# SerialController.net
KiCad netlist of a schematic drawn in EAGLE
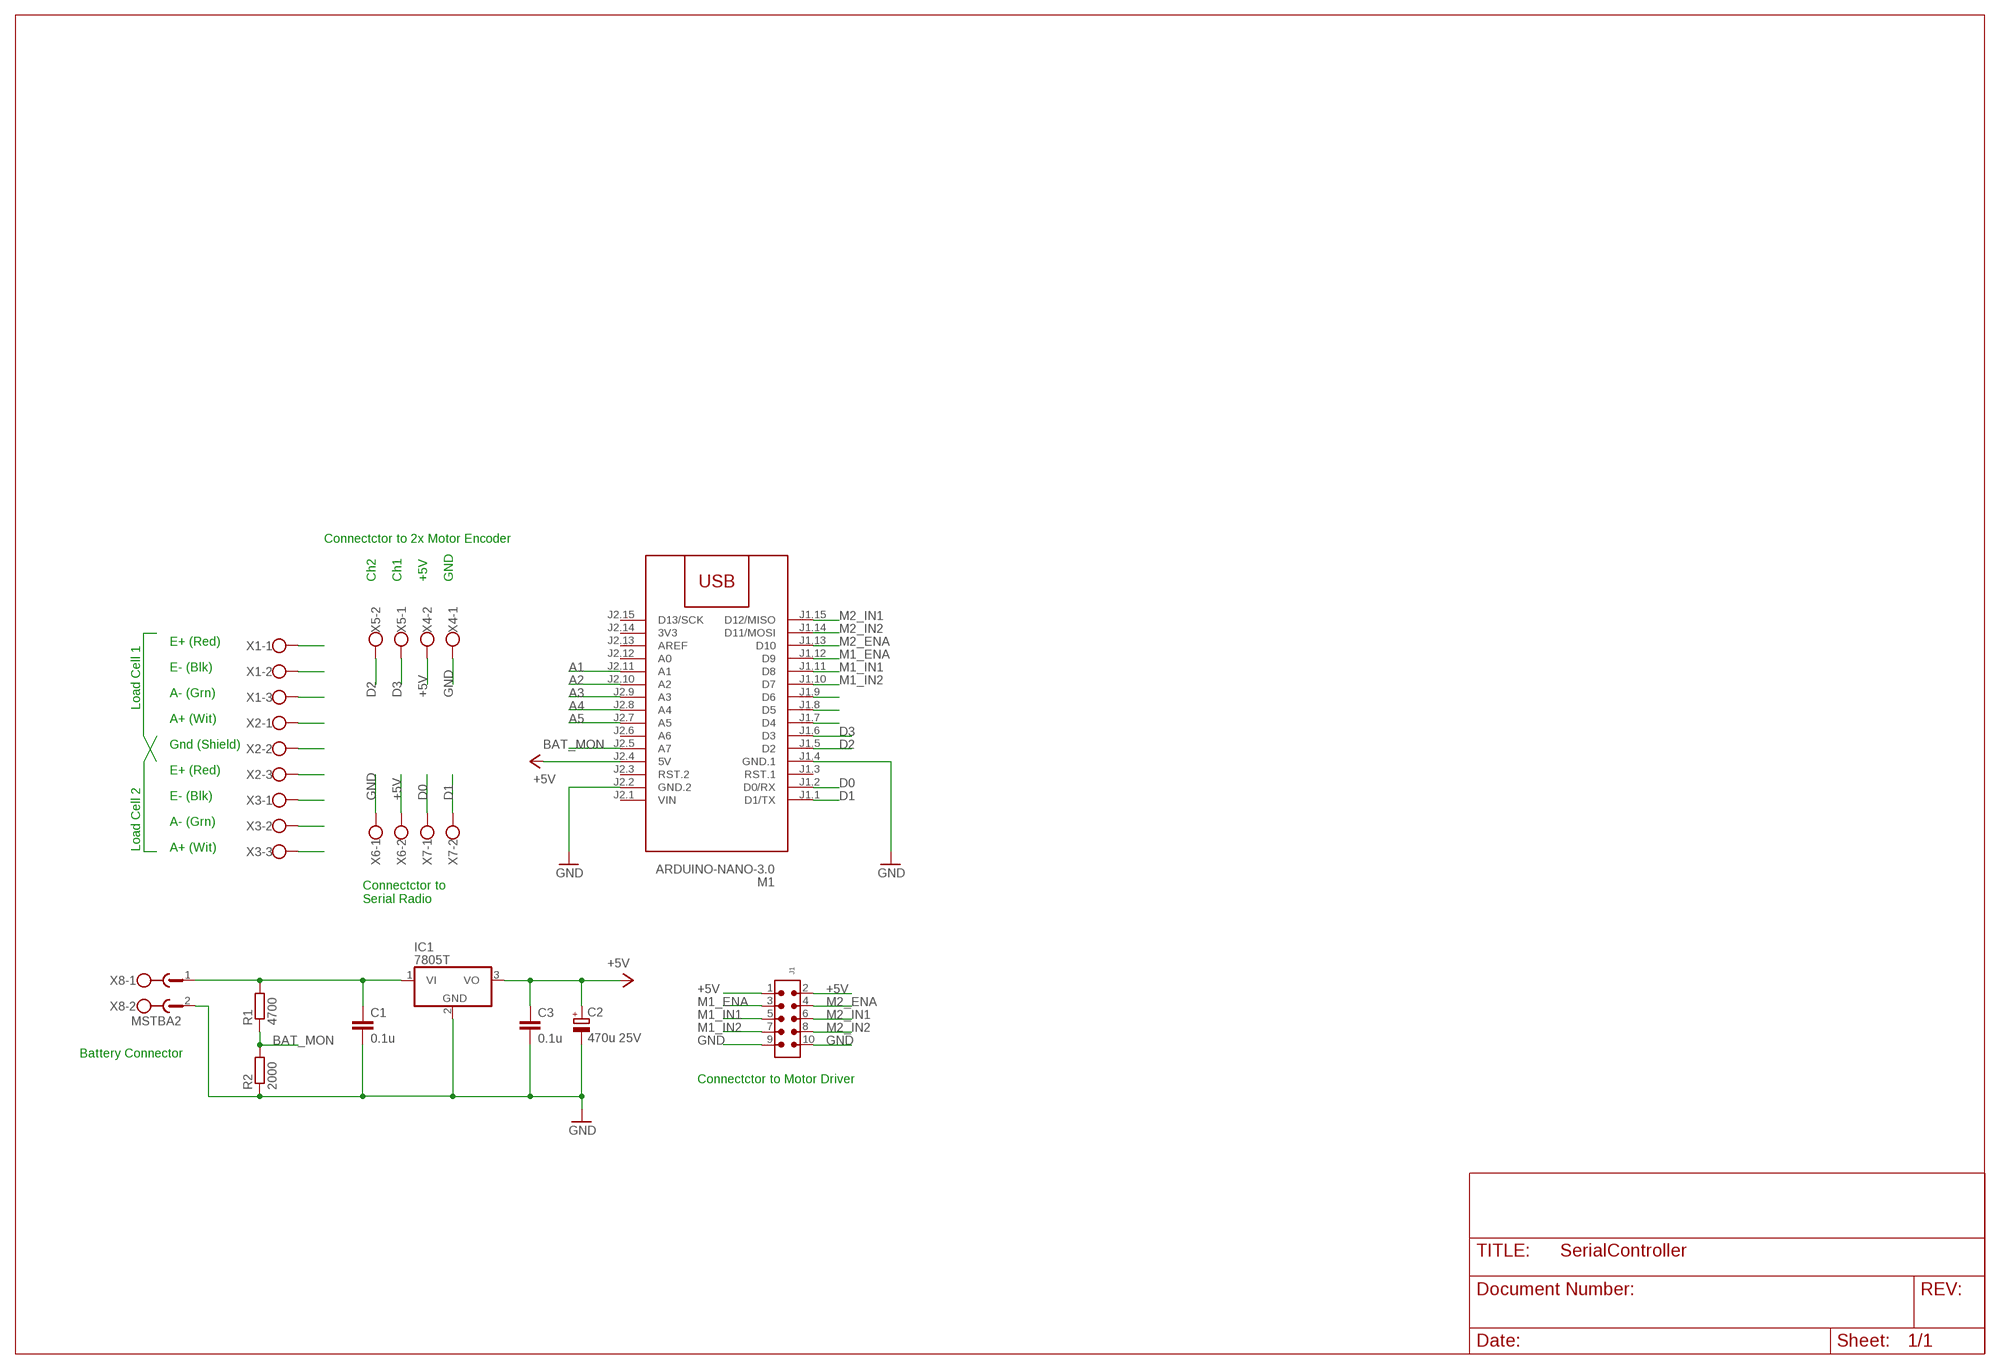
[diagram p0: schematic, sheet 1]

(export (version "E")
  (design (tool "Eeschema 10.0.6"))
  (components
    (comp (ref "C1")
      (value "0.1u")
      (footprint "eagle-import:C050-030X075")
      (libsource (lib "eagle-import") (part "C-EU050-030X075"))
    )
    (comp (ref "C2")
      (value "470u 25V")
      (footprint "eagle-import:EB20D")
      (libsource (lib "eagle-import") (part "CPOL-EUE10-20"))
    )
    (comp (ref "C3")
      (value "0.1u")
      (footprint "eagle-import:C050-030X075")
      (libsource (lib "eagle-import") (part "C-EU050-030X075"))
    )
    (comp (ref "IC1")
      (value "7805T")
      (footprint "eagle-import:TO220H")
      (libsource (lib "eagle-import") (part "78T05"))
    )
    (comp (ref "J1")
      (value "6120XX21621_61201021621")
      (footprint "eagle-import:61201021621")
      (libsource (lib "eagle-import") (part "6120XX21621_61201021621"))
    )
    (comp (ref "M1")
      (value "ARDUINO-NANO-3.0")
      (footprint "eagle-import:ARDUINO-NANO-3.0")
      (libsource (lib "eagle-import") (part "ARDUINO-NANO-3.0"))
    )
    (comp (ref "R1")
      (value "4700")
      (footprint "eagle-import:0207_12")
      (libsource (lib "eagle-import") (part "R-EU_0207/12"))
    )
    (comp (ref "R2")
      (value "2000")
      (footprint "eagle-import:0207_7")
      (libsource (lib "eagle-import") (part "R-EU_0207/7"))
    )
    (comp (ref "X1")
      (value "W237-103")
      (footprint "eagle-import:W237-103")
      (fields (field (name "MPN") "237-103"))
      (libsource (lib "eagle-import") (part "W237-103"))
    )
    (comp (ref "X2")
      (value "W237-103")
      (footprint "eagle-import:W237-103")
      (fields (field (name "MPN") "237-103"))
      (libsource (lib "eagle-import") (part "W237-103"))
    )
    (comp (ref "X3")
      (value "W237-103")
      (footprint "eagle-import:W237-103")
      (fields (field (name "MPN") "237-103"))
      (libsource (lib "eagle-import") (part "W237-103"))
    )
    (comp (ref "X4")
      (value "W237-102")
      (footprint "eagle-import:W237-102")
      (fields (field (name "MPN") "237-102"))
      (libsource (lib "eagle-import") (part "W237-102"))
    )
    (comp (ref "X5")
      (value "W237-102")
      (footprint "eagle-import:W237-102")
      (fields (field (name "MPN") "237-102"))
      (libsource (lib "eagle-import") (part "W237-102"))
    )
    (comp (ref "X6")
      (value "W237-102")
      (footprint "eagle-import:W237-102")
      (fields (field (name "MPN") "237-102"))
      (libsource (lib "eagle-import") (part "W237-102"))
    )
    (comp (ref "X7")
      (value "W237-102")
      (footprint "eagle-import:W237-102")
      (fields (field (name "MPN") "237-102"))
      (libsource (lib "eagle-import") (part "W237-102"))
    )
    (comp (ref "X8")
      (value "MSTBA2")
      (footprint "eagle-import:MSTBA2")
      (fields (field (name "MF") "FARNELL") (field (name "MPN") "1757242"))
      (libsource (lib "eagle-import") (part "MSTBA2"))
    )
  )
  (nets
    (net (code "1") (name "+5V") (class "Default")
      (node (ref "C2") (pin "+") (pinfunction "+_+") (pintype "passive"))
      (node (ref "C3") (pin "1") (pinfunction "1_1") (pintype "passive"))
      (node (ref "IC1") (pin "3") (pinfunction "VO_3") (pintype "passive"))
      (node (ref "J1") (pin "1") (pinfunction "1_1") (pintype "passive"))
      (node (ref "J1") (pin "2") (pinfunction "2_2") (pintype "passive"))
      (node (ref "M1") (pin "J2.4") (pinfunction "5V_J2.4") (pintype "power_in"))
      (node (ref "X4") (pin "2") (pinfunction "KL_2") (pintype "passive"))
      (node (ref "X6") (pin "2") (pinfunction "KL_2") (pintype "passive"))
    )
    (net (code "2") (name "/3V3") (class "Default")
      (node (ref "M1") (pin "J2.14") (pinfunction "3V3_J2.14") (pintype "power_in"))
    )
    (net (code "3") (name "/A1") (class "Default")
      (node (ref "M1") (pin "J2.11") (pinfunction "A1_J2.11") (pintype "bidirectional"))
    )
    (net (code "4") (name "/A2") (class "Default")
      (node (ref "M1") (pin "J2.10") (pinfunction "A2_J2.10") (pintype "bidirectional"))
    )
    (net (code "5") (name "/A3") (class "Default")
      (node (ref "M1") (pin "J2.9") (pinfunction "A3_J2.9") (pintype "bidirectional"))
    )
    (net (code "6") (name "/A4") (class "Default")
      (node (ref "M1") (pin "J2.8") (pinfunction "A4_J2.8") (pintype "bidirectional"))
    )
    (net (code "7") (name "/A5") (class "Default")
      (node (ref "M1") (pin "J2.7") (pinfunction "A5_J2.7") (pintype "bidirectional"))
    )
    (net (code "8") (name "/BAT_MON") (class "Default")
      (node (ref "M1") (pin "J2.5") (pinfunction "A7_J2.5") (pintype "bidirectional"))
      (node (ref "R1") (pin "1") (pinfunction "1_1") (pintype "passive"))
      (node (ref "R2") (pin "2") (pinfunction "2_2") (pintype "passive"))
    )
    (net (code "9") (name "/D0") (class "Default")
      (node (ref "M1") (pin "J1.2") (pinfunction "D0/RX_J1.2") (pintype "bidirectional"))
      (node (ref "X7") (pin "1") (pinfunction "KL_1") (pintype "passive"))
    )
    (net (code "10") (name "/D1") (class "Default")
      (node (ref "M1") (pin "J1.1") (pinfunction "D1/TX_J1.1") (pintype "bidirectional"))
      (node (ref "X7") (pin "2") (pinfunction "KL_2") (pintype "passive"))
    )
    (net (code "11") (name "/D2") (class "Default")
      (node (ref "M1") (pin "J1.5") (pinfunction "D2_J1.5") (pintype "bidirectional"))
      (node (ref "X5") (pin "2") (pinfunction "KL_2") (pintype "passive"))
    )
    (net (code "12") (name "/D3") (class "Default")
      (node (ref "M1") (pin "J1.6") (pinfunction "D3_J1.6") (pintype "bidirectional"))
      (node (ref "X5") (pin "1") (pinfunction "KL_1") (pintype "passive"))
    )
    (net (code "13") (name "/M1_ENA") (class "Default")
      (node (ref "J1") (pin "3") (pinfunction "3_3") (pintype "passive"))
      (node (ref "M1") (pin "J1.12") (pinfunction "D9_J1.12") (pintype "bidirectional"))
    )
    (net (code "14") (name "/M1_IN1") (class "Default")
      (node (ref "J1") (pin "5") (pinfunction "5_5") (pintype "passive"))
      (node (ref "M1") (pin "J1.11") (pinfunction "D8_J1.11") (pintype "bidirectional"))
    )
    (net (code "15") (name "/M1_IN2") (class "Default")
      (node (ref "J1") (pin "7") (pinfunction "7_7") (pintype "passive"))
      (node (ref "M1") (pin "J1.10") (pinfunction "D7_J1.10") (pintype "bidirectional"))
    )
    (net (code "16") (name "/M2_ENA") (class "Default")
      (node (ref "J1") (pin "4") (pinfunction "4_4") (pintype "passive"))
      (node (ref "M1") (pin "J1.13") (pinfunction "D10_J1.13") (pintype "bidirectional"))
    )
    (net (code "17") (name "/M2_IN1") (class "Default")
      (node (ref "J1") (pin "6") (pinfunction "6_6") (pintype "passive"))
      (node (ref "M1") (pin "J1.15") (pinfunction "D12/MISO_J1.15") (pintype "bidirectional"))
    )
    (net (code "18") (name "/M2_IN2") (class "Default")
      (node (ref "J1") (pin "8") (pinfunction "8_8") (pintype "passive"))
      (node (ref "M1") (pin "J1.14") (pinfunction "D11/MOSI_J1.14") (pintype "bidirectional"))
    )
    (net (code "19") (name "/VIN") (class "Default")
      (node (ref "M1") (pin "J2.1") (pinfunction "VIN_J2.1") (pintype "power_in"))
    )
    (net (code "20") (name "GND") (class "Default")
      (node (ref "C1") (pin "2") (pinfunction "2_2") (pintype "passive"))
      (node (ref "C2") (pin "-") (pinfunction "-_-") (pintype "passive"))
      (node (ref "C3") (pin "2") (pinfunction "2_2") (pintype "passive"))
      (node (ref "IC1") (pin "2") (pinfunction "GND_2") (pintype "passive"))
      (node (ref "J1") (pin "10") (pinfunction "10_10") (pintype "passive"))
      (node (ref "J1") (pin "9") (pinfunction "9_9") (pintype "passive"))
      (node (ref "M1") (pin "J1.4") (pinfunction "GND.1_J1.4") (pintype "power_in"))
      (node (ref "M1") (pin "J2.2") (pinfunction "GND.2_J2.2") (pintype "power_in"))
      (node (ref "R2") (pin "1") (pinfunction "1_1") (pintype "passive"))
      (node (ref "X4") (pin "1") (pinfunction "KL_1") (pintype "passive"))
      (node (ref "X6") (pin "1") (pinfunction "KL_1") (pintype "passive"))
      (node (ref "X8") (pin "2") (pinfunction "1_2") (pintype "passive"))
    )
    (net (code "21") (name "Net-(IC1-VI)") (class "Default")
      (node (ref "C1") (pin "1") (pinfunction "1_1") (pintype "passive"))
      (node (ref "IC1") (pin "1") (pinfunction "VI_1") (pintype "input"))
      (node (ref "R1") (pin "2") (pinfunction "2_2") (pintype "passive"))
      (node (ref "X8") (pin "1") (pinfunction "1_1") (pintype "passive"))
    )
    (net (code "22") (name "unconnected-(M1-A0-PadJ2.12)") (class "Default")
      (node (ref "M1") (pin "J2.12") (pinfunction "A0_J2.12") (pintype "bidirectional"))
    )
    (net (code "23") (name "unconnected-(M1-A6-PadJ2.6)") (class "Default")
      (node (ref "M1") (pin "J2.6") (pinfunction "A6_J2.6") (pintype "bidirectional"))
    )
    (net (code "24") (name "unconnected-(M1-AREF-PadJ2.13)") (class "Default")
      (node (ref "M1") (pin "J2.13") (pinfunction "AREF_J2.13") (pintype "bidirectional"))
    )
    (net (code "25") (name "unconnected-(M1-D4-PadJ1.7)") (class "Default")
      (node (ref "M1") (pin "J1.7") (pinfunction "D4_J1.7") (pintype "bidirectional"))
    )
    (net (code "26") (name "unconnected-(M1-D5-PadJ1.8)") (class "Default")
      (node (ref "M1") (pin "J1.8") (pinfunction "D5_J1.8") (pintype "bidirectional"))
    )
    (net (code "27") (name "unconnected-(M1-D6-PadJ1.9)") (class "Default")
      (node (ref "M1") (pin "J1.9") (pinfunction "D6_J1.9") (pintype "bidirectional"))
    )
    (net (code "28") (name "unconnected-(M1-D13{slash}SCK-PadJ2.15)") (class "Default")
      (node (ref "M1") (pin "J2.15") (pinfunction "D13/SCK_J2.15") (pintype "bidirectional"))
    )
    (net (code "29") (name "unconnected-(M1-RST.1-PadJ1.3)") (class "Default")
      (node (ref "M1") (pin "J1.3") (pinfunction "RST.1_J1.3") (pintype "bidirectional"))
    )
    (net (code "30") (name "unconnected-(M1-RST.2-PadJ2.3)") (class "Default")
      (node (ref "M1") (pin "J2.3") (pinfunction "RST.2_J2.3") (pintype "bidirectional"))
    )
    (net (code "31") (name "unconnected-(X1A-KL-Pad1)") (class "Default")
      (node (ref "X1") (pin "1") (pinfunction "KL_1") (pintype "passive"))
    )
    (net (code "32") (name "unconnected-(X1B-KL-Pad2)") (class "Default")
      (node (ref "X1") (pin "2") (pinfunction "KL_2") (pintype "passive"))
    )
    (net (code "33") (name "unconnected-(X1C-KL-Pad3)") (class "Default")
      (node (ref "X1") (pin "3") (pinfunction "KL_3") (pintype "passive"))
    )
    (net (code "34") (name "unconnected-(X2A-KL-Pad1)") (class "Default")
      (node (ref "X2") (pin "1") (pinfunction "KL_1") (pintype "passive"))
    )
    (net (code "35") (name "unconnected-(X2B-KL-Pad2)") (class "Default")
      (node (ref "X2") (pin "2") (pinfunction "KL_2") (pintype "passive"))
    )
    (net (code "36") (name "unconnected-(X2C-KL-Pad3)") (class "Default")
      (node (ref "X2") (pin "3") (pinfunction "KL_3") (pintype "passive"))
    )
    (net (code "37") (name "unconnected-(X3A-KL-Pad1)") (class "Default")
      (node (ref "X3") (pin "1") (pinfunction "KL_1") (pintype "passive"))
    )
    (net (code "38") (name "unconnected-(X3B-KL-Pad2)") (class "Default")
      (node (ref "X3") (pin "2") (pinfunction "KL_2") (pintype "passive"))
    )
    (net (code "39") (name "unconnected-(X3C-KL-Pad3)") (class "Default")
      (node (ref "X3") (pin "3") (pinfunction "KL_3") (pintype "passive"))
    )
  )
)
